# Headphone-Amplifier-ClassAB-smallest.net
KiCad netlist of a schematic drawn in EAGLE
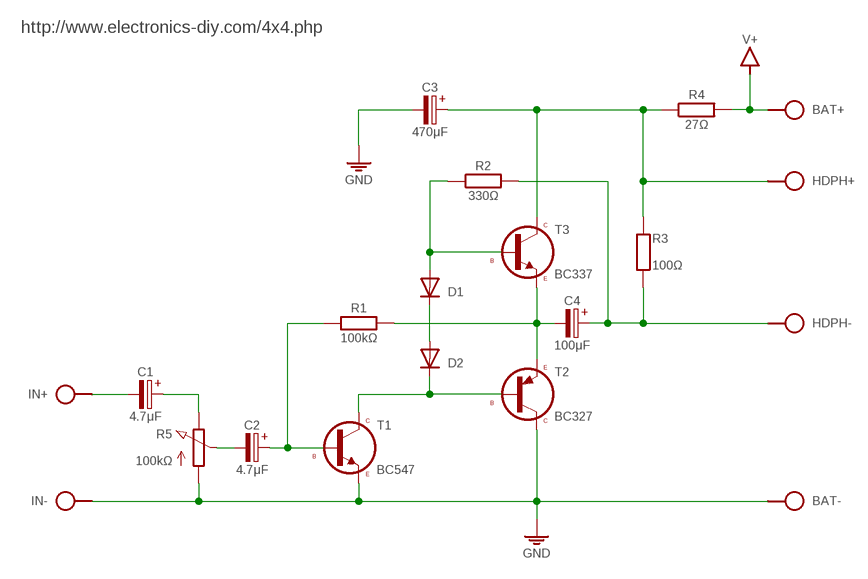
[diagram p0: schematic, sheet 1]

(export (version "E")
  (design (tool "Eeschema 10.0.6"))
  (components
    (comp (ref "BAT")
      (value "SPAD+-+-")
      (footprint "eagle-import:SPAD+-")
      (libsource (lib "eagle-import") (part "SPAD+-+-"))
    )
    (comp (ref "C1")
      (value "4.7μF")
      (footprint "eagle-import:E2,5-4")
      (libsource (lib "eagle-import") (part "CPOLE2,5-4"))
    )
    (comp (ref "C2")
      (value "4.7μF")
      (footprint "eagle-import:E2,5-4")
      (libsource (lib "eagle-import") (part "CPOLE2,5-4"))
    )
    (comp (ref "C3")
      (value "470μF")
      (footprint "eagle-import:E5-4-R45")
      (libsource (lib "eagle-import") (part "CPOLE5-4-R45"))
    )
    (comp (ref "C4")
      (value "100μF")
      (footprint "eagle-import:E5-4")
      (libsource (lib "eagle-import") (part "CPOLE5-4"))
    )
    (comp (ref "D1")
      (value "1N414834-5V")
      (footprint "eagle-import:DO34-5V")
      (libsource (lib "eagle-import") (part "1N414834-5V"))
    )
    (comp (ref "D2")
      (value "1N414834-5V")
      (footprint "eagle-import:DO34-5V")
      (libsource (lib "eagle-import") (part "1N414834-5V"))
    )
    (comp (ref "HDPH")
      (value "SPAD+--+")
      (footprint "eagle-import:SPAD-+")
      (libsource (lib "eagle-import") (part "SPAD+--+"))
    )
    (comp (ref "IN")
      (value "SPAD+--+")
      (footprint "eagle-import:SPAD-+")
      (libsource (lib "eagle-import") (part "SPAD+--+"))
    )
    (comp (ref "R1")
      (value "100kΩ")
      (footprint "eagle-import:0202_5")
      (libsource (lib "eagle-import") (part "R-H0202/5"))
    )
    (comp (ref "R2")
      (value "330Ω")
      (footprint "eagle-import:0202_7")
      (libsource (lib "eagle-import") (part "R-H0202/7"))
    )
    (comp (ref "R3")
      (value "100Ω")
      (footprint "eagle-import:0202_7")
      (libsource (lib "eagle-import") (part "R0202/7"))
    )
    (comp (ref "R4")
      (value "27Ω")
      (footprint "eagle-import:0204V")
      (libsource (lib "eagle-import") (part "R-H-V-X"))
    )
    (comp (ref "R5")
      (value "100kΩ")
      (footprint "eagle-import:CONN-3P")
      (libsource (lib "eagle-import") (part "POT-3P"))
    )
    (comp (ref "T1")
      (value "BC547")
      (footprint "eagle-import:TO92")
      (libsource (lib "eagle-import") (part "BC547"))
    )
    (comp (ref "T2")
      (value "BC327")
      (footprint "eagle-import:TO92")
      (libsource (lib "eagle-import") (part "BC327"))
    )
    (comp (ref "T3")
      (value "BC337")
      (footprint "eagle-import:TO92-CBE")
      (libsource (lib "eagle-import") (part "BC337CBE"))
    )
  )
  (nets
    (net (code "1") (name "GND") (class "Default")
      (node (ref "BAT") (pin "1") (pinfunction "P$1_1") (pintype "passive"))
      (node (ref "C3") (pin "-") (pinfunction "-_-") (pintype "passive"))
      (node (ref "IN") (pin "1") (pinfunction "P$1_1") (pintype "passive"))
      (node (ref "R5") (pin "1") (pinfunction "A_1") (pintype "passive"))
      (node (ref "T1") (pin "3") (pinfunction "E_3") (pintype "passive"))
      (node (ref "T2") (pin "1") (pinfunction "C_1") (pintype "passive"))
    )
    (net (code "2") (name "Net-(D1-PadC)") (class "Default")
      (node (ref "D1") (pin "C") (pinfunction "C_C") (pintype "passive"))
      (node (ref "D2") (pin "A") (pinfunction "A_A") (pintype "passive"))
    )
    (net (code "3") (name "Net-(HDPHA-P$1)") (class "Default")
      (node (ref "C3") (pin "+") (pinfunction "+_+") (pintype "passive"))
      (node (ref "HDPH") (pin "2") (pinfunction "P$1_2") (pintype "passive"))
      (node (ref "R3") (pin "2") (pinfunction "1_2") (pintype "passive"))
      (node (ref "R4") (pin "2") (pinfunction "1_2") (pintype "passive"))
      (node (ref "T3") (pin "1") (pinfunction "C_1") (pintype "passive"))
    )
    (net (code "4") (name "Net-(HDPHB-P$1)") (class "Default")
      (node (ref "C4") (pin "+") (pinfunction "+_+") (pintype "passive"))
      (node (ref "HDPH") (pin "1") (pinfunction "P$1_1") (pintype "passive"))
      (node (ref "R2") (pin "2") (pinfunction "2_2") (pintype "passive"))
      (node (ref "R3") (pin "1") (pinfunction "2_1") (pintype "passive"))
    )
    (net (code "5") (name "Net-(INA-P$1)") (class "Default")
      (node (ref "C1") (pin "-") (pinfunction "-_-") (pintype "passive"))
      (node (ref "IN") (pin "2") (pinfunction "P$1_2") (pintype "passive"))
    )
    (net (code "6") (name "Net-(R5-E)") (class "Default")
      (node (ref "C1") (pin "+") (pinfunction "+_+") (pintype "passive"))
      (node (ref "R5") (pin "3") (pinfunction "E_3") (pintype "passive"))
    )
    (net (code "7") (name "Net-(R5-S)") (class "Default")
      (node (ref "C2") (pin "-") (pinfunction "-_-") (pintype "passive"))
      (node (ref "R5") (pin "2") (pinfunction "S_2") (pintype "passive"))
    )
    (net (code "8") (name "Net-(T1-B)") (class "Default")
      (node (ref "C2") (pin "+") (pinfunction "+_+") (pintype "passive"))
      (node (ref "R1") (pin "1") (pinfunction "1_1") (pintype "passive"))
      (node (ref "T1") (pin "2") (pinfunction "B_2") (pintype "passive"))
    )
    (net (code "9") (name "Net-(T1-C)") (class "Default")
      (node (ref "D2") (pin "C") (pinfunction "C_C") (pintype "passive"))
      (node (ref "T1") (pin "1") (pinfunction "C_1") (pintype "passive"))
      (node (ref "T2") (pin "2") (pinfunction "B_2") (pintype "passive"))
    )
    (net (code "10") (name "Net-(T2-E)") (class "Default")
      (node (ref "C4") (pin "-") (pinfunction "-_-") (pintype "passive"))
      (node (ref "R1") (pin "2") (pinfunction "2_2") (pintype "passive"))
      (node (ref "T2") (pin "3") (pinfunction "E_3") (pintype "passive"))
      (node (ref "T3") (pin "3") (pinfunction "E_3") (pintype "passive"))
    )
    (net (code "11") (name "Net-(T3-B)") (class "Default")
      (node (ref "D1") (pin "A") (pinfunction "A_A") (pintype "passive"))
      (node (ref "R2") (pin "1") (pinfunction "1_1") (pintype "passive"))
      (node (ref "T3") (pin "2") (pinfunction "B_2") (pintype "passive"))
    )
    (net (code "12") (name "V+") (class "Default")
      (node (ref "BAT") (pin "2") (pinfunction "P$1_2") (pintype "passive"))
      (node (ref "R4") (pin "1") (pinfunction "2_1") (pintype "passive"))
    )
  )
)
